# CHANNEL_DELAY.net
KiCad netlist of a schematic drawn in Altium Designer
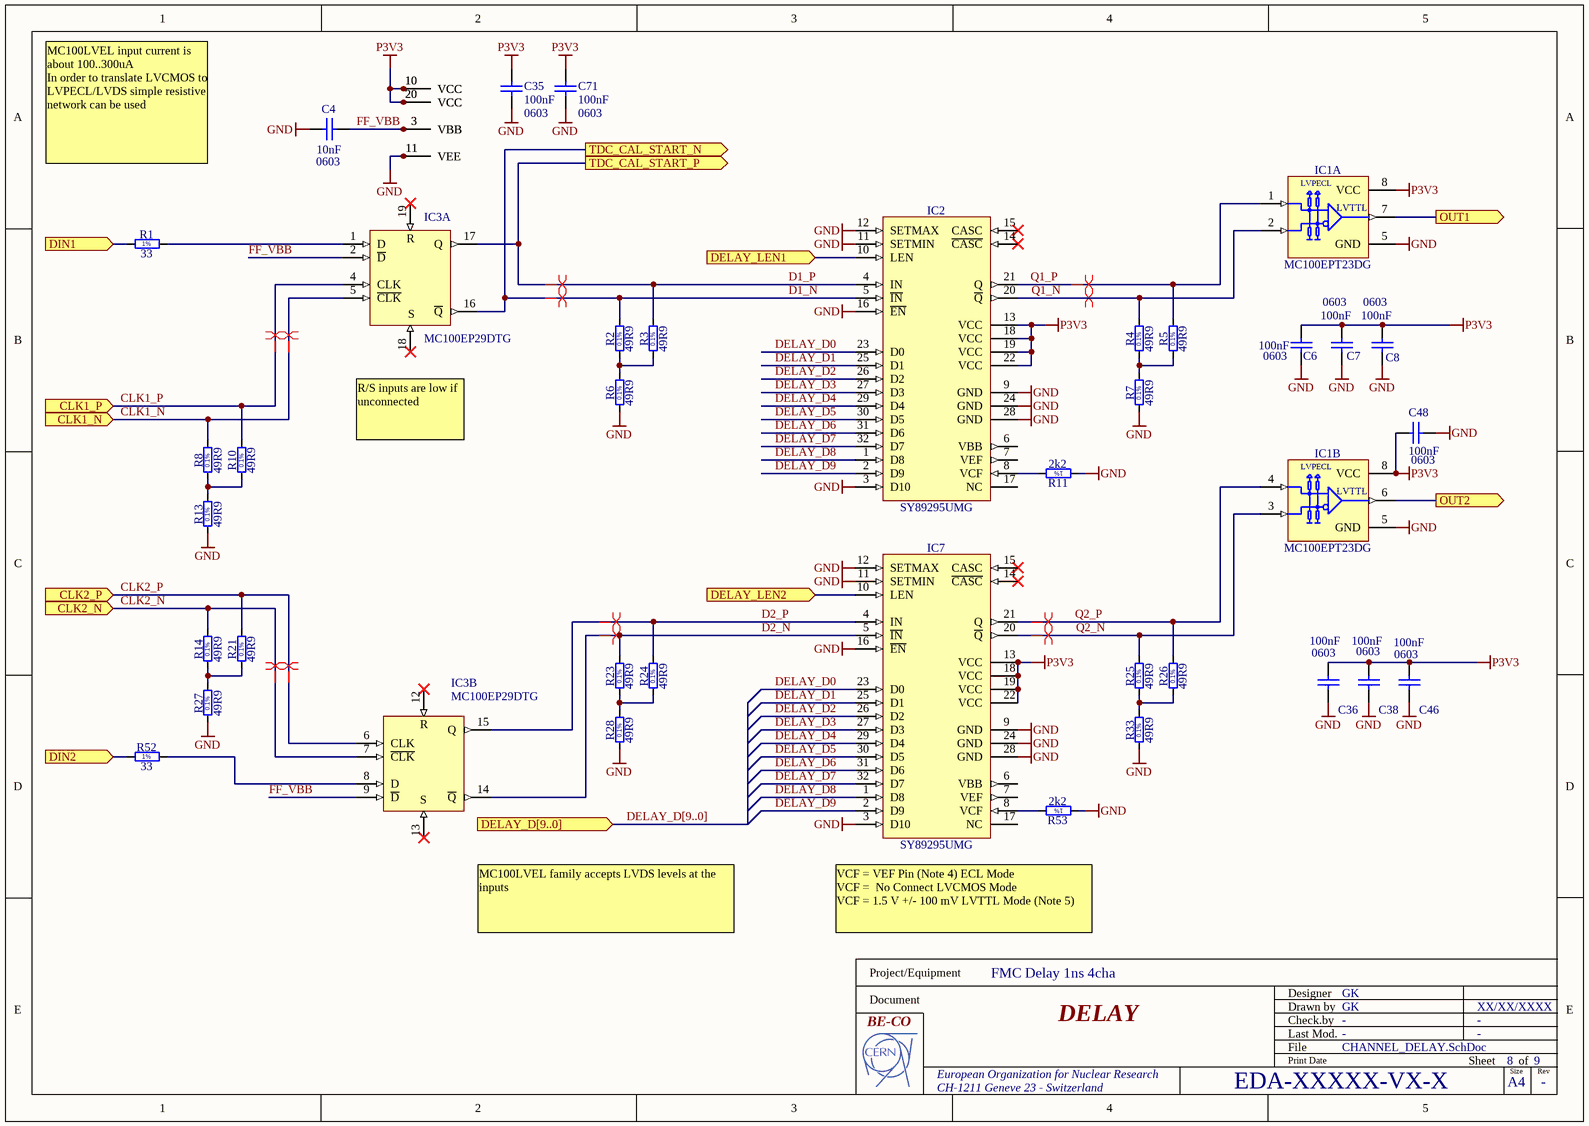
[diagram p0: CHANNEL_DELAY.SchDoc]

(export (version "E")
  (design (tool "Eeschema 10.0.6"))
  (components
    (comp (ref "C4")
      (value "10nF")
      (footprint "CAPC1608X87N")
      (description "Non-polarised capacitor")
      (fields
        (field (name "PART NUMBER") "CC0603_10NF_50V_10%_X7R")
        (field (name "VOLTAGE") "50V")
        (field (name "CASE") "0603")
        (field (name "AUTHOR") "CERN DEM JLC")
      )
      (libsource (lib "Capacitors") (part "Capacitor - non polarized"))
    )
    (comp (ref "C6")
      (value "100nF")
      (footprint "CAPC1608X87N")
      (description "Non-polarised capacitor")
      (fields
        (field (name "CASE") "0603")
        (field (name "MANUFACTURER1 PART NUMBER") "223858615649")
        (field (name "MANUFACTURER") "GENERIC")
        (field (name "AUTHOR") "CERN DEM JLC")
      )
      (libsource (lib "Capacitors") (part "Capacitor - non polarized"))
    )
    (comp (ref "C7")
      (value "100nF")
      (footprint "CAPC1608X87N")
      (description "Non-polarised capacitor")
      (fields
        (field (name "CASE") "0603")
        (field (name "MANUFACTURER1 PART NUMBER") "223858615649")
        (field (name "MANUFACTURER") "GENERIC")
        (field (name "AUTHOR") "CERN DEM JLC")
      )
      (libsource (lib "Capacitors") (part "Capacitor - non polarized"))
    )
    (comp (ref "C8")
      (value "100nF")
      (footprint "CAPC1608X87N")
      (description "Non-polarised capacitor")
      (fields
        (field (name "CASE") "0603")
        (field (name "MANUFACTURER1 PART NUMBER") "223858615649")
        (field (name "MANUFACTURER") "GENERIC")
        (field (name "AUTHOR") "CERN DEM JLC")
      )
      (libsource (lib "Capacitors") (part "Capacitor - non polarized"))
    )
    (comp (ref "C35")
      (value "100nF")
      (footprint "CAPC1608X87N")
      (description "Non-polarised capacitor")
      (fields
        (field (name "CASE") "0603")
        (field (name "MANUFACTURER1 PART NUMBER") "223858615649")
        (field (name "MANUFACTURER") "GENERIC")
        (field (name "AUTHOR") "CERN DEM JLC")
      )
      (libsource (lib "Capacitors") (part "Capacitor - non polarized"))
    )
    (comp (ref "C36")
      (value "100nF")
      (footprint "CAPC1608X87N")
      (description "Non-polarised capacitor")
      (fields
        (field (name "CASE") "0603")
        (field (name "MANUFACTURER1 PART NUMBER") "223858615649")
        (field (name "MANUFACTURER") "GENERIC")
        (field (name "AUTHOR") "CERN DEM JLC")
      )
      (libsource (lib "Capacitors") (part "Capacitor - non polarized"))
    )
    (comp (ref "C38")
      (value "100nF")
      (footprint "CAPC1608X87N")
      (description "Non-polarised capacitor")
      (fields
        (field (name "CASE") "0603")
        (field (name "MANUFACTURER1 PART NUMBER") "223858615649")
        (field (name "MANUFACTURER") "GENERIC")
        (field (name "AUTHOR") "CERN DEM JLC")
      )
      (libsource (lib "Capacitors") (part "Capacitor - non polarized"))
    )
    (comp (ref "C46")
      (value "100nF")
      (footprint "CAPC1608X87N")
      (description "Non-polarised capacitor")
      (fields
        (field (name "CASE") "0603")
        (field (name "MANUFACTURER1 PART NUMBER") "223858615649")
        (field (name "MANUFACTURER") "GENERIC")
        (field (name "AUTHOR") "CERN DEM JLC")
      )
      (libsource (lib "Capacitors") (part "Capacitor - non polarized"))
    )
    (comp (ref "C48")
      (value "100nF")
      (footprint "CAPC1608X87N")
      (description "Non-polarised capacitor")
      (fields
        (field (name "CASE") "0603")
        (field (name "MANUFACTURER1 PART NUMBER") "223858615649")
        (field (name "MANUFACTURER") "GENERIC")
        (field (name "AUTHOR") "CERN DEM JLC")
      )
      (libsource (lib "Capacitors") (part "Capacitor - non polarized"))
    )
    (comp (ref "C71")
      (value "100nF")
      (footprint "CAPC1608X87N")
      (description "Non-polarised capacitor")
      (fields
        (field (name "CASE") "0603")
        (field (name "MANUFACTURER1 PART NUMBER") "223858615649")
        (field (name "MANUFACTURER") "GENERIC")
        (field (name "AUTHOR") "CERN DEM JLC")
      )
      (libsource (lib "Capacitors") (part "Capacitor - non polarized"))
    )
    (comp (ref "IC1")
      (value "MC100EPT23DG")
      (footprint "SOIC127P600X175-8N")
      (description "3.3V Dual Differential LVPECL/LVDS/CML  to LVTTL/LVCMOS Translator")
      (fields (field (name "MANUFACTURER") "ON SEMICONDUCTOR") (field (name "AUTHOR") "CERN DEM JLC"))
      (libsource (lib "ICs And Semiconductors") (part "100EPT23D"))
    )
    (comp (ref "IC2")
      (value "SY89295UMG")
      (footprint "QFN50P500X500X90-33N-S320")
      (description "2.5V/3.3V 1.5GHz Precision LVPECL Programmable Delay")
      (fields (field (name "MANUFACTURER") "MICREL") (field (name "AUTHOR") "CERN DEM JLC"))
      (libsource (lib "ICs And Semiconductors") (part "SY89295UMG"))
    )
    (comp (ref "IC3")
      (value "MC100EP29DTG")
      (footprint "SOP65P640X120-20N")
      (description "3.3V/5V ECL Dual Differential Data and Clock D Flip-Flop With Set and Reset")
      (fields (field (name "MANUFACTURER") "ON SEMICONDUCTOR") (field (name "AUTHOR") "CERN DEM JLC"))
      (libsource (lib "") (part "100EP29D_1"))
    )
    (comp (ref "IC7")
      (value "SY89295UMG")
      (footprint "QFN50P500X500X90-33N-S320")
      (description "2.5V/3.3V 1.5GHz Precision LVPECL Programmable Delay")
      (fields (field (name "MANUFACTURER") "MICREL") (field (name "AUTHOR") "CERN DEM JLC"))
      (libsource (lib "ICs And Semiconductors") (part "SY89295UMG"))
    )
    (comp (ref "R1")
      (value "33")
      (footprint "RESC1608X55N")
      (description "Resistor - 1%")
      (fields
        (field (name "PART NUMBER") "R0603_33R_1%_0.1W_100PPM")
        (field (name "POWER") "0.1W")
        (field (name "AUTHOR") "CERN DEM JLC")
      )
      (libsource (lib "Resistors") (part "Resistor - 1%"))
    )
    (comp (ref "R2")
      (value "49R9")
      (footprint "RESC1608X55N")
      (description "Resistor - 0.1%")
      (fields
        (field (name "PART NUMBER") "R0603_49R9_0.1%_0.063W_10PPM")
        (field (name "POWER") "0.063W")
        (field (name "AUTHOR") "CERN DEM JLC")
      )
      (libsource (lib "Resistors") (part "Resistor - 0.1%"))
    )
    (comp (ref "R3")
      (value "49R9")
      (footprint "RESC1608X55N")
      (description "Resistor - 0.1%")
      (fields
        (field (name "PART NUMBER") "R0603_49R9_0.1%_0.063W_10PPM")
        (field (name "POWER") "0.063W")
        (field (name "AUTHOR") "CERN DEM JLC")
      )
      (libsource (lib "Resistors") (part "Resistor - 0.1%"))
    )
    (comp (ref "R4")
      (value "49R9")
      (footprint "RESC1608X55N")
      (description "Resistor - 0.1%")
      (fields
        (field (name "PART NUMBER") "R0603_49R9_0.1%_0.063W_10PPM")
        (field (name "POWER") "0.063W")
        (field (name "AUTHOR") "CERN DEM JLC")
      )
      (libsource (lib "Resistors") (part "Resistor - 0.1%"))
    )
    (comp (ref "R5")
      (value "49R9")
      (footprint "RESC1608X55N")
      (description "Resistor - 0.1%")
      (fields
        (field (name "PART NUMBER") "R0603_49R9_0.1%_0.063W_10PPM")
        (field (name "POWER") "0.063W")
        (field (name "AUTHOR") "CERN DEM JLC")
      )
      (libsource (lib "Resistors") (part "Resistor - 0.1%"))
    )
    (comp (ref "R6")
      (value "49R9")
      (footprint "RESC1608X55N")
      (description "Resistor - 0.1%")
      (fields
        (field (name "PART NUMBER") "R0603_49R9_0.1%_0.063W_10PPM")
        (field (name "POWER") "0.063W")
        (field (name "AUTHOR") "CERN DEM JLC")
      )
      (libsource (lib "Resistors") (part "Resistor - 0.1%"))
    )
    (comp (ref "R7")
      (value "49R9")
      (footprint "RESC1608X55N")
      (description "Resistor - 0.1%")
      (fields
        (field (name "PART NUMBER") "R0603_49R9_0.1%_0.063W_10PPM")
        (field (name "POWER") "0.063W")
        (field (name "AUTHOR") "CERN DEM JLC")
      )
      (libsource (lib "Resistors") (part "Resistor - 0.1%"))
    )
    (comp (ref "R8")
      (value "49R9")
      (footprint "RESC1608X55N")
      (description "Resistor - 0.1%")
      (fields
        (field (name "PART NUMBER") "R0603_49R9_0.1%_0.063W_10PPM")
        (field (name "POWER") "0.063W")
        (field (name "AUTHOR") "CERN DEM JLC")
      )
      (libsource (lib "Resistors") (part "Resistor - 0.1%"))
    )
    (comp (ref "R10")
      (value "49R9")
      (footprint "RESC1608X55N")
      (description "Resistor - 0.1%")
      (fields
        (field (name "PART NUMBER") "R0603_49R9_0.1%_0.063W_10PPM")
        (field (name "POWER") "0.063W")
        (field (name "AUTHOR") "CERN DEM JLC")
      )
      (libsource (lib "Resistors") (part "Resistor - 0.1%"))
    )
    (comp (ref "R11")
      (value "2k2")
      (footprint "RESC1608X55N")
      (description "Resistor - 1%")
      (fields
        (field (name "PART NUMBER") "R0603_2K2_1%_0.1W_100PPM")
        (field (name "POWER") "0.1W")
        (field (name "AUTHOR") "CERN DEM JLC")
      )
      (libsource (lib "Resistors") (part "Resistor - 1%"))
    )
    (comp (ref "R13")
      (value "49R9")
      (footprint "RESC1608X55N")
      (description "Resistor - 0.1%")
      (fields
        (field (name "PART NUMBER") "R0603_49R9_0.1%_0.063W_10PPM")
        (field (name "POWER") "0.063W")
        (field (name "AUTHOR") "CERN DEM JLC")
      )
      (libsource (lib "Resistors") (part "Resistor - 0.1%"))
    )
    (comp (ref "R14")
      (value "49R9")
      (footprint "RESC1608X55N")
      (description "Resistor - 0.1%")
      (fields
        (field (name "PART NUMBER") "R0603_49R9_0.1%_0.063W_10PPM")
        (field (name "POWER") "0.063W")
        (field (name "AUTHOR") "CERN DEM JLC")
      )
      (libsource (lib "Resistors") (part "Resistor - 0.1%"))
    )
    (comp (ref "R21")
      (value "49R9")
      (footprint "RESC1608X55N")
      (description "Resistor - 0.1%")
      (fields
        (field (name "PART NUMBER") "R0603_49R9_0.1%_0.063W_10PPM")
        (field (name "POWER") "0.063W")
        (field (name "AUTHOR") "CERN DEM JLC")
      )
      (libsource (lib "Resistors") (part "Resistor - 0.1%"))
    )
    (comp (ref "R23")
      (value "49R9")
      (footprint "RESC1608X55N")
      (description "Resistor - 0.1%")
      (fields
        (field (name "PART NUMBER") "R0603_49R9_0.1%_0.063W_10PPM")
        (field (name "POWER") "0.063W")
        (field (name "AUTHOR") "CERN DEM JLC")
      )
      (libsource (lib "Resistors") (part "Resistor - 0.1%"))
    )
    (comp (ref "R24")
      (value "49R9")
      (footprint "RESC1608X55N")
      (description "Resistor - 0.1%")
      (fields
        (field (name "PART NUMBER") "R0603_49R9_0.1%_0.063W_10PPM")
        (field (name "POWER") "0.063W")
        (field (name "AUTHOR") "CERN DEM JLC")
      )
      (libsource (lib "Resistors") (part "Resistor - 0.1%"))
    )
    (comp (ref "R25")
      (value "49R9")
      (footprint "RESC1608X55N")
      (description "Resistor - 0.1%")
      (fields
        (field (name "PART NUMBER") "R0603_49R9_0.1%_0.063W_10PPM")
        (field (name "POWER") "0.063W")
        (field (name "AUTHOR") "CERN DEM JLC")
      )
      (libsource (lib "Resistors") (part "Resistor - 0.1%"))
    )
    (comp (ref "R26")
      (value "49R9")
      (footprint "RESC1608X55N")
      (description "Resistor - 0.1%")
      (fields
        (field (name "PART NUMBER") "R0603_49R9_0.1%_0.063W_10PPM")
        (field (name "POWER") "0.063W")
        (field (name "AUTHOR") "CERN DEM JLC")
      )
      (libsource (lib "Resistors") (part "Resistor - 0.1%"))
    )
    (comp (ref "R27")
      (value "49R9")
      (footprint "RESC1608X55N")
      (description "Resistor - 0.1%")
      (fields
        (field (name "PART NUMBER") "R0603_49R9_0.1%_0.063W_10PPM")
        (field (name "POWER") "0.063W")
        (field (name "AUTHOR") "CERN DEM JLC")
      )
      (libsource (lib "Resistors") (part "Resistor - 0.1%"))
    )
    (comp (ref "R28")
      (value "49R9")
      (footprint "RESC1608X55N")
      (description "Resistor - 0.1%")
      (fields
        (field (name "PART NUMBER") "R0603_49R9_0.1%_0.063W_10PPM")
        (field (name "POWER") "0.063W")
        (field (name "AUTHOR") "CERN DEM JLC")
      )
      (libsource (lib "Resistors") (part "Resistor - 0.1%"))
    )
    (comp (ref "R33")
      (value "49R9")
      (footprint "RESC1608X55N")
      (description "Resistor - 0.1%")
      (fields
        (field (name "PART NUMBER") "R0603_49R9_0.1%_0.063W_10PPM")
        (field (name "POWER") "0.063W")
        (field (name "AUTHOR") "CERN DEM JLC")
      )
      (libsource (lib "Resistors") (part "Resistor - 0.1%"))
    )
    (comp (ref "R52")
      (value "33")
      (footprint "RESC1608X55N")
      (description "Resistor - 1%")
      (fields
        (field (name "PART NUMBER") "R0603_33R_1%_0.1W_100PPM")
        (field (name "POWER") "0.1W")
        (field (name "AUTHOR") "CERN DEM JLC")
      )
      (libsource (lib "Resistors") (part "Resistor - 1%"))
    )
    (comp (ref "R53")
      (value "2k2")
      (footprint "RESC1608X55N")
      (description "Resistor - 1%")
      (fields
        (field (name "PART NUMBER") "R0603_2K2_1%_0.1W_100PPM")
        (field (name "POWER") "0.1W")
        (field (name "AUTHOR") "CERN DEM JLC")
      )
      (libsource (lib "Resistors") (part "Resistor - 1%"))
    )
  )
  (nets
    (net (code "1") (name "/CLK1_N") (class "Default")
      (node (ref "IC3") (pin "5") (pinfunction "~{CLK}_5") (pintype "input"))
      (node (ref "R8") (pin "2") (pinfunction "2_2") (pintype "passive"))
    )
    (net (code "2") (name "/CLK1_P") (class "Default")
      (node (ref "IC3") (pin "4") (pinfunction "CLK_4") (pintype "input"))
      (node (ref "R10") (pin "2") (pinfunction "2_2") (pintype "passive"))
    )
    (net (code "3") (name "/CLK2_N") (class "Default")
      (node (ref "IC3") (pin "7") (pinfunction "~{CLK}_7") (pintype "input"))
      (node (ref "R14") (pin "2") (pinfunction "2_2") (pintype "passive"))
    )
    (net (code "4") (name "/CLK2_P") (class "Default")
      (node (ref "IC3") (pin "6") (pinfunction "CLK_6") (pintype "input"))
      (node (ref "R21") (pin "2") (pinfunction "2_2") (pintype "passive"))
    )
    (net (code "5") (name "/D1_N") (class "Default")
      (node (ref "IC2") (pin "5") (pinfunction "~{IN}_5") (pintype "input"))
      (node (ref "IC3") (pin "16") (pinfunction "~{Q}_16") (pintype "output"))
      (node (ref "R2") (pin "2") (pinfunction "2_2") (pintype "passive"))
    )
    (net (code "6") (name "/D1_P") (class "Default")
      (node (ref "IC2") (pin "4") (pinfunction "IN_4") (pintype "input"))
      (node (ref "IC3") (pin "17") (pinfunction "Q_17") (pintype "output"))
      (node (ref "R3") (pin "2") (pinfunction "2_2") (pintype "passive"))
    )
    (net (code "7") (name "/D2_N") (class "Default")
      (node (ref "IC3") (pin "14") (pinfunction "~{Q}_14") (pintype "output"))
      (node (ref "IC7") (pin "5") (pinfunction "~{IN}_5") (pintype "input"))
      (node (ref "R23") (pin "2") (pinfunction "2_2") (pintype "passive"))
    )
    (net (code "8") (name "/D2_P") (class "Default")
      (node (ref "IC3") (pin "15") (pinfunction "Q_15") (pintype "output"))
      (node (ref "IC7") (pin "4") (pinfunction "IN_4") (pintype "input"))
      (node (ref "R24") (pin "2") (pinfunction "2_2") (pintype "passive"))
    )
    (net (code "9") (name "/DELAY_D0") (class "Default")
      (node (ref "IC2") (pin "23") (pinfunction "D0_23") (pintype "input"))
      (node (ref "IC7") (pin "23") (pinfunction "D0_23") (pintype "input"))
    )
    (net (code "10") (name "/DELAY_D1") (class "Default")
      (node (ref "IC2") (pin "25") (pinfunction "D1_25") (pintype "input"))
      (node (ref "IC7") (pin "25") (pinfunction "D1_25") (pintype "input"))
    )
    (net (code "11") (name "/DELAY_D2") (class "Default")
      (node (ref "IC2") (pin "26") (pinfunction "D2_26") (pintype "input"))
      (node (ref "IC7") (pin "26") (pinfunction "D2_26") (pintype "input"))
    )
    (net (code "12") (name "/DELAY_D3") (class "Default")
      (node (ref "IC2") (pin "27") (pinfunction "D3_27") (pintype "input"))
      (node (ref "IC7") (pin "27") (pinfunction "D3_27") (pintype "input"))
    )
    (net (code "13") (name "/DELAY_D4") (class "Default")
      (node (ref "IC2") (pin "29") (pinfunction "D4_29") (pintype "input"))
      (node (ref "IC7") (pin "29") (pinfunction "D4_29") (pintype "input"))
    )
    (net (code "14") (name "/DELAY_D5") (class "Default")
      (node (ref "IC2") (pin "30") (pinfunction "D5_30") (pintype "input"))
      (node (ref "IC7") (pin "30") (pinfunction "D5_30") (pintype "input"))
    )
    (net (code "15") (name "/DELAY_D6") (class "Default")
      (node (ref "IC2") (pin "31") (pinfunction "D6_31") (pintype "input"))
      (node (ref "IC7") (pin "31") (pinfunction "D6_31") (pintype "input"))
    )
    (net (code "16") (name "/DELAY_D7") (class "Default")
      (node (ref "IC2") (pin "32") (pinfunction "D7_32") (pintype "input"))
      (node (ref "IC7") (pin "32") (pinfunction "D7_32") (pintype "input"))
    )
    (net (code "17") (name "/DELAY_D8") (class "Default")
      (node (ref "IC2") (pin "1") (pinfunction "D8_1") (pintype "input"))
      (node (ref "IC7") (pin "1") (pinfunction "D8_1") (pintype "input"))
    )
    (net (code "18") (name "/DELAY_D9") (class "Default")
      (node (ref "IC2") (pin "2") (pinfunction "D9_2") (pintype "input"))
      (node (ref "IC7") (pin "2") (pinfunction "D9_2") (pintype "input"))
    )
    (net (code "20") (name "/DELAY_LEN1") (class "Default")
      (node (ref "IC2") (pin "10") (pinfunction "LEN_10") (pintype "input"))
    )
    (net (code "21") (name "/DELAY_LEN2") (class "Default")
      (node (ref "IC7") (pin "10") (pinfunction "LEN_10") (pintype "input"))
    )
    (net (code "22") (name "/DIN1") (class "Default")
      (node (ref "R1") (pin "1") (pinfunction "1_1") (pintype "passive"))
    )
    (net (code "23") (name "/DIN2") (class "Default")
      (node (ref "R52") (pin "1") (pinfunction "1_1") (pintype "passive"))
    )
    (net (code "24") (name "/OUT1") (class "Default")
      (node (ref "IC1") (pin "7") (pinfunction "Q0_7") (pintype "output"))
    )
    (net (code "25") (name "/OUT2") (class "Default")
      (node (ref "IC1") (pin "6") (pinfunction "Q0_6") (pintype "output"))
    )
    (net (code "26") (name "/Q1_N") (class "Default")
      (node (ref "IC1") (pin "2") (pinfunction "~{D0}_2") (pintype "input"))
      (node (ref "IC2") (pin "20") (pinfunction "~{Q}_20") (pintype "output"))
      (node (ref "R4") (pin "2") (pinfunction "2_2") (pintype "passive"))
    )
    (net (code "27") (name "/Q1_P") (class "Default")
      (node (ref "IC1") (pin "1") (pinfunction "D0_1") (pintype "input"))
      (node (ref "IC2") (pin "21") (pinfunction "Q_21") (pintype "output"))
      (node (ref "R5") (pin "2") (pinfunction "2_2") (pintype "passive"))
    )
    (net (code "28") (name "/Q2_N") (class "Default")
      (node (ref "IC1") (pin "3") (pinfunction "~{D0}_3") (pintype "input"))
      (node (ref "IC7") (pin "20") (pinfunction "~{Q}_20") (pintype "output"))
      (node (ref "R25") (pin "2") (pinfunction "2_2") (pintype "passive"))
    )
    (net (code "29") (name "/Q2_P") (class "Default")
      (node (ref "IC1") (pin "4") (pinfunction "D0_4") (pintype "input"))
      (node (ref "IC7") (pin "21") (pinfunction "Q_21") (pintype "output"))
      (node (ref "R26") (pin "2") (pinfunction "2_2") (pintype "passive"))
    )
    (net (code "30") (name "GND") (class "Default")
      (node (ref "C35") (pin "1") (pinfunction "1_1") (pintype "passive"))
      (node (ref "C36") (pin "2") (pinfunction "2_2") (pintype "passive"))
      (node (ref "C38") (pin "2") (pinfunction "2_2") (pintype "passive"))
      (node (ref "C4") (pin "2") (pinfunction "2_2") (pintype "passive"))
      (node (ref "C46") (pin "2") (pinfunction "2_2") (pintype "passive"))
      (node (ref "C48") (pin "2") (pinfunction "2_2") (pintype "passive"))
      (node (ref "C6") (pin "2") (pinfunction "2_2") (pintype "passive"))
      (node (ref "C7") (pin "2") (pinfunction "2_2") (pintype "passive"))
      (node (ref "C71") (pin "1") (pinfunction "1_1") (pintype "passive"))
      (node (ref "C8") (pin "2") (pinfunction "2_2") (pintype "passive"))
      (node (ref "IC1") (pin "5") (pinfunction "GND_5") (pintype "power_in"))
      (node (ref "IC2") (pin "11") (pinfunction "SETMIN_11") (pintype "input"))
      (node (ref "IC2") (pin "12") (pinfunction "SETMAX_12") (pintype "input"))
      (node (ref "IC2") (pin "16") (pinfunction "~{EN}_16") (pintype "input"))
      (node (ref "IC2") (pin "24") (pinfunction "GND_24") (pintype "power_in"))
      (node (ref "IC2") (pin "28") (pinfunction "GND_28") (pintype "power_in"))
      (node (ref "IC2") (pin "3") (pinfunction "D10_3") (pintype "input"))
      (node (ref "IC2") (pin "9") (pinfunction "GND_9") (pintype "power_in"))
      (node (ref "IC3") (pin "11") (pinfunction "VEE_11") (pintype "power_in"))
      (node (ref "IC7") (pin "11") (pinfunction "SETMIN_11") (pintype "input"))
      (node (ref "IC7") (pin "12") (pinfunction "SETMAX_12") (pintype "input"))
      (node (ref "IC7") (pin "16") (pinfunction "~{EN}_16") (pintype "input"))
      (node (ref "IC7") (pin "24") (pinfunction "GND_24") (pintype "power_in"))
      (node (ref "IC7") (pin "28") (pinfunction "GND_28") (pintype "power_in"))
      (node (ref "IC7") (pin "3") (pinfunction "D10_3") (pintype "input"))
      (node (ref "IC7") (pin "9") (pinfunction "GND_9") (pintype "power_in"))
      (node (ref "R11") (pin "1") (pinfunction "1_1") (pintype "passive"))
      (node (ref "R13") (pin "1") (pinfunction "1_1") (pintype "passive"))
      (node (ref "R27") (pin "1") (pinfunction "1_1") (pintype "passive"))
      (node (ref "R28") (pin "1") (pinfunction "1_1") (pintype "passive"))
      (node (ref "R33") (pin "1") (pinfunction "1_1") (pintype "passive"))
      (node (ref "R53") (pin "1") (pinfunction "1_1") (pintype "passive"))
      (node (ref "R6") (pin "1") (pinfunction "1_1") (pintype "passive"))
      (node (ref "R7") (pin "1") (pinfunction "1_1") (pintype "passive"))
    )
    (net (code "31") (name "Net-(IC2-VCF)") (class "Default")
      (node (ref "IC2") (pin "8") (pinfunction "VCF_8") (pintype "input"))
      (node (ref "R11") (pin "2") (pinfunction "2_2") (pintype "passive"))
    )
    (net (code "32") (name "Net-(IC3A-D)") (class "Default")
      (node (ref "IC3") (pin "1") (pinfunction "D_1") (pintype "input"))
      (node (ref "R1") (pin "2") (pinfunction "2_2") (pintype "passive"))
    )
    (net (code "33") (name "Net-(IC3B-D)") (class "Default")
      (node (ref "IC3") (pin "8") (pinfunction "D_8") (pintype "input"))
      (node (ref "R52") (pin "2") (pinfunction "2_2") (pintype "passive"))
    )
    (net (code "34") (name "Net-(IC7-VCF)") (class "Default")
      (node (ref "IC7") (pin "8") (pinfunction "VCF_8") (pintype "input"))
      (node (ref "R53") (pin "2") (pinfunction "2_2") (pintype "passive"))
    )
    (net (code "35") (name "Net-(R2-Pad1)") (class "Default")
      (node (ref "R2") (pin "1") (pinfunction "1_1") (pintype "passive"))
      (node (ref "R3") (pin "1") (pinfunction "1_1") (pintype "passive"))
      (node (ref "R6") (pin "2") (pinfunction "2_2") (pintype "passive"))
    )
    (net (code "36") (name "Net-(R4-Pad1)") (class "Default")
      (node (ref "R4") (pin "1") (pinfunction "1_1") (pintype "passive"))
      (node (ref "R5") (pin "1") (pinfunction "1_1") (pintype "passive"))
      (node (ref "R7") (pin "2") (pinfunction "2_2") (pintype "passive"))
    )
    (net (code "37") (name "Net-(R10-Pad1)") (class "Default")
      (node (ref "R10") (pin "1") (pinfunction "1_1") (pintype "passive"))
      (node (ref "R13") (pin "2") (pinfunction "2_2") (pintype "passive"))
      (node (ref "R8") (pin "1") (pinfunction "1_1") (pintype "passive"))
    )
    (net (code "38") (name "Net-(R14-Pad1)") (class "Default")
      (node (ref "R14") (pin "1") (pinfunction "1_1") (pintype "passive"))
      (node (ref "R21") (pin "1") (pinfunction "1_1") (pintype "passive"))
      (node (ref "R27") (pin "2") (pinfunction "2_2") (pintype "passive"))
    )
    (net (code "39") (name "Net-(R23-Pad1)") (class "Default")
      (node (ref "R23") (pin "1") (pinfunction "1_1") (pintype "passive"))
      (node (ref "R24") (pin "1") (pinfunction "1_1") (pintype "passive"))
      (node (ref "R28") (pin "2") (pinfunction "2_2") (pintype "passive"))
    )
    (net (code "40") (name "Net-(R25-Pad1)") (class "Default")
      (node (ref "R25") (pin "1") (pinfunction "1_1") (pintype "passive"))
      (node (ref "R26") (pin "1") (pinfunction "1_1") (pintype "passive"))
      (node (ref "R33") (pin "2") (pinfunction "2_2") (pintype "passive"))
    )
    (net (code "41") (name "P3V3") (class "Default")
      (node (ref "C35") (pin "2") (pinfunction "2_2") (pintype "passive"))
      (node (ref "C36") (pin "1") (pinfunction "1_1") (pintype "passive"))
      (node (ref "C38") (pin "1") (pinfunction "1_1") (pintype "passive"))
      (node (ref "C46") (pin "1") (pinfunction "1_1") (pintype "passive"))
      (node (ref "C48") (pin "1") (pinfunction "1_1") (pintype "passive"))
      (node (ref "C6") (pin "1") (pinfunction "1_1") (pintype "passive"))
      (node (ref "C7") (pin "1") (pinfunction "1_1") (pintype "passive"))
      (node (ref "C71") (pin "2") (pinfunction "2_2") (pintype "passive"))
      (node (ref "C8") (pin "1") (pinfunction "1_1") (pintype "passive"))
      (node (ref "IC1") (pin "8") (pinfunction "VCC_8") (pintype "power_in"))
      (node (ref "IC2") (pin "13") (pinfunction "VCC_13") (pintype "power_in"))
      (node (ref "IC2") (pin "18") (pinfunction "VCC_18") (pintype "power_in"))
      (node (ref "IC2") (pin "19") (pinfunction "VCC_19") (pintype "power_in"))
      (node (ref "IC2") (pin "22") (pinfunction "VCC_22") (pintype "power_in"))
      (node (ref "IC3") (pin "10") (pinfunction "VCC_10") (pintype "power_in"))
      (node (ref "IC3") (pin "20") (pinfunction "VCC_20") (pintype "power_in"))
      (node (ref "IC7") (pin "13") (pinfunction "VCC_13") (pintype "power_in"))
      (node (ref "IC7") (pin "18") (pinfunction "VCC_18") (pintype "power_in"))
      (node (ref "IC7") (pin "19") (pinfunction "VCC_19") (pintype "power_in"))
      (node (ref "IC7") (pin "22") (pinfunction "VCC_22") (pintype "power_in"))
    )
    (net (code "42") (name "VBB") (class "Default")
      (node (ref "C4") (pin "1") (pinfunction "1_1") (pintype "passive"))
      (node (ref "IC3") (pin "2") (pinfunction "~{D}_2") (pintype "input"))
      (node (ref "IC3") (pin "3") (pinfunction "VBB_3") (pintype "power_in"))
      (node (ref "IC3") (pin "9") (pinfunction "~{D}_9") (pintype "input"))
    )
    (net (code "43") (name "unconnected-(IC2-CASC-Pad15)") (class "Default")
      (node (ref "IC2") (pin "15") (pinfunction "CASC_15") (pintype "input+no_connect"))
    )
    (net (code "44") (name "unconnected-(IC2-NC-Pad17)") (class "Default")
      (node (ref "IC2") (pin "17") (pinfunction "NC_17") (pintype "passive"))
    )
    (net (code "45") (name "unconnected-(IC2-VBB-Pad6)") (class "Default")
      (node (ref "IC2") (pin "6") (pinfunction "VBB_6") (pintype "output"))
    )
    (net (code "46") (name "unconnected-(IC2-VEF-Pad7)") (class "Default")
      (node (ref "IC2") (pin "7") (pinfunction "VEF_7") (pintype "output"))
    )
    (net (code "47") (name "unconnected-(IC2-~{CASC}-Pad14)") (class "Default")
      (node (ref "IC2") (pin "14") (pinfunction "~{CASC}_14") (pintype "input+no_connect"))
    )
    (net (code "48") (name "unconnected-(IC3A-R-Pad19)") (class "Default")
      (node (ref "IC3") (pin "19") (pinfunction "R_19") (pintype "input+no_connect"))
    )
    (net (code "49") (name "unconnected-(IC3A-S-Pad18)") (class "Default")
      (node (ref "IC3") (pin "18") (pinfunction "S_18") (pintype "input+no_connect"))
    )
    (net (code "50") (name "unconnected-(IC3B-R-Pad12)") (class "Default")
      (node (ref "IC3") (pin "12") (pinfunction "R_12") (pintype "input+no_connect"))
    )
    (net (code "51") (name "unconnected-(IC3B-S-Pad13)") (class "Default")
      (node (ref "IC3") (pin "13") (pinfunction "S_13") (pintype "input+no_connect"))
    )
    (net (code "52") (name "unconnected-(IC7-CASC-Pad15)") (class "Default")
      (node (ref "IC7") (pin "15") (pinfunction "CASC_15") (pintype "input+no_connect"))
    )
    (net (code "53") (name "unconnected-(IC7-NC-Pad17)") (class "Default")
      (node (ref "IC7") (pin "17") (pinfunction "NC_17") (pintype "passive"))
    )
    (net (code "54") (name "unconnected-(IC7-VBB-Pad6)") (class "Default")
      (node (ref "IC7") (pin "6") (pinfunction "VBB_6") (pintype "output"))
    )
    (net (code "55") (name "unconnected-(IC7-VEF-Pad7)") (class "Default")
      (node (ref "IC7") (pin "7") (pinfunction "VEF_7") (pintype "output"))
    )
    (net (code "56") (name "unconnected-(IC7-~{CASC}-Pad14)") (class "Default")
      (node (ref "IC7") (pin "14") (pinfunction "~{CASC}_14") (pintype "input+no_connect"))
    )
  )
)
